# Endstops.net
KiCad netlist of a schematic drawn in Altium Designer
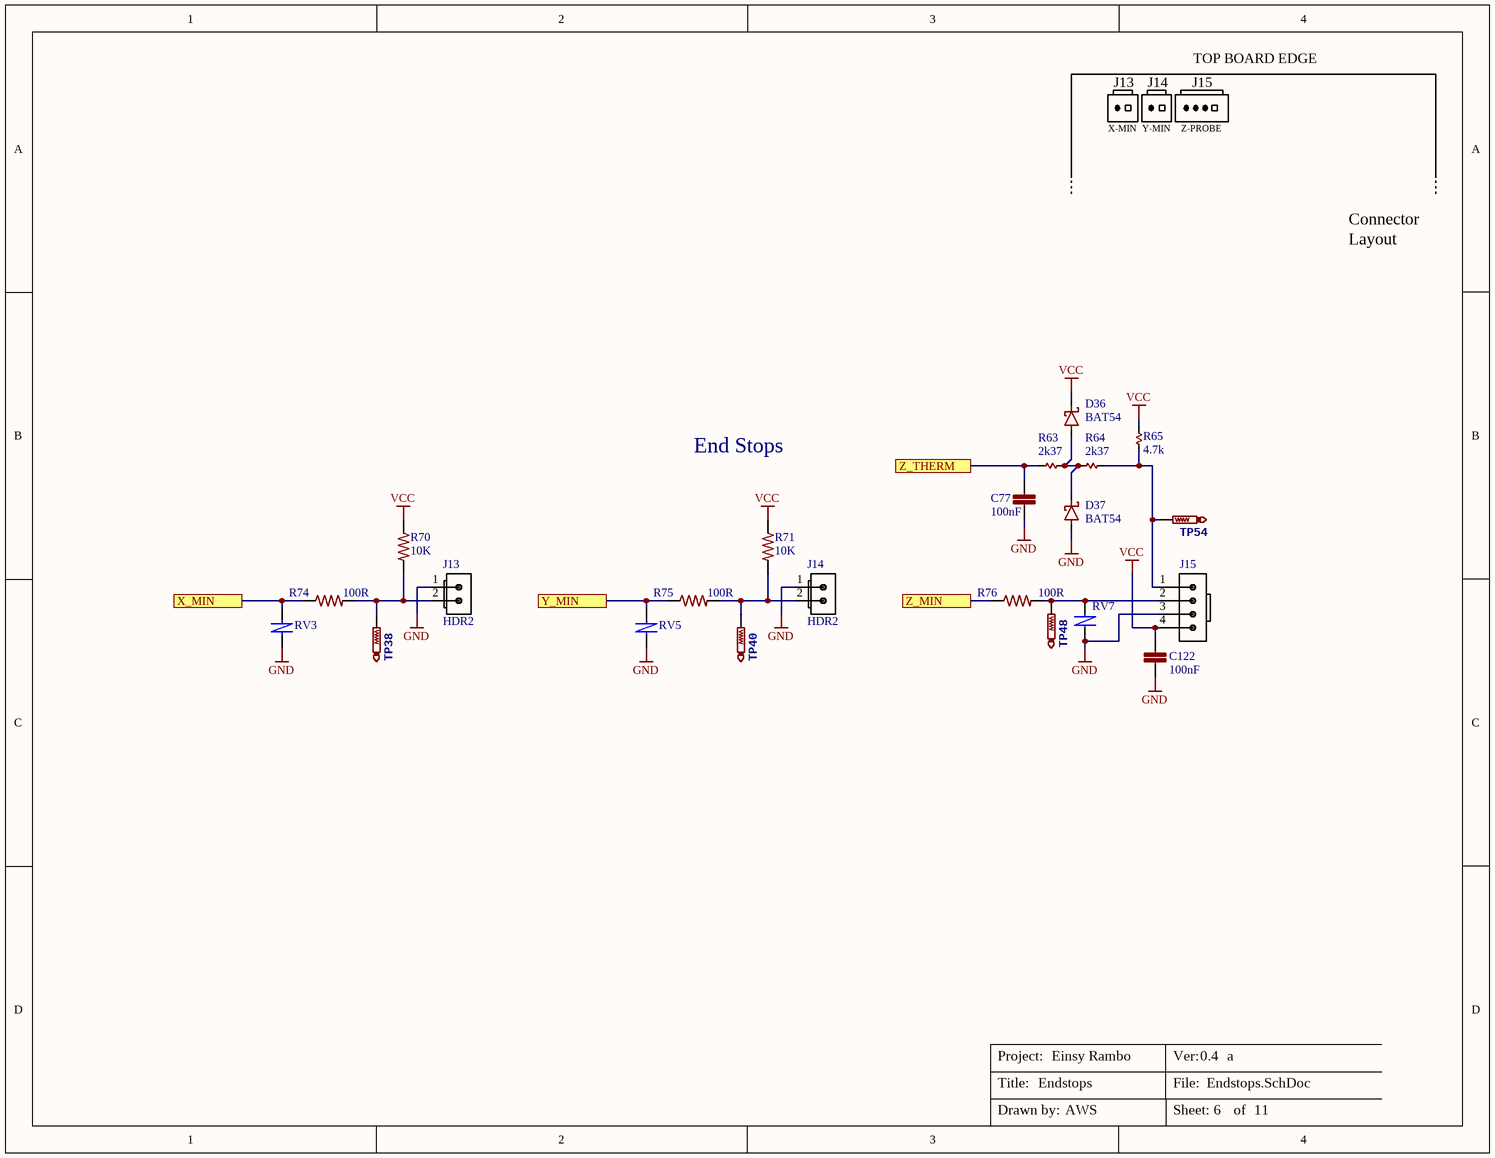
[diagram p0: Endstops.SchDoc]

(export (version "E")
  (design (tool "Eeschema 10.0.6"))
  (components
    (comp (ref "C77")
      (value "100nF")
      (footprint "C0402")
      (description "CAP CER 0402 100nF 16V 10% X7R")
      (fields (field (name "MANUFACTURER") "Murata") (field (name "TOLERANCE") "+/- 10%"))
      (libsource (lib "") (part "GRM155R71C104KA88D_1"))
    )
    (comp (ref "C122")
      (value "100nF")
      (footprint "C0402")
      (description "CAP CER 0402 100nF 16V 10% X7R")
      (fields (field (name "MANUFACTURER") "Murata") (field (name "TOLERANCE") "+/- 10%"))
      (libsource (lib "3Delight") (part "GRM155R71C104KA88D"))
    )
    (comp (ref "D36")
      (value "BAT54")
      (footprint "SOD523_IPC")
      (description "Diode Schottky 30V 100mA Surface Mount SOD-523")
      (fields (field (name "MANUFACTURER") "Diodes Incorporated") (field (name "TOLERANCE") "NA"))
      (libsource (lib "3Delight") (part "BAT54WT-7"))
    )
    (comp (ref "D37")
      (value "BAT54")
      (footprint "SOD523_IPC")
      (description "Diode Schottky 30V 100mA Surface Mount SOD-523")
      (fields (field (name "MANUFACTURER") "Diodes Incorporated") (field (name "TOLERANCE") "NA"))
      (libsource (lib "3Delight") (part "BAT54WT-7"))
    )
    (comp (ref "J13")
      (value "HDR2")
      (footprint "70543-02 PIN-IN-PASTE")
      (description "Connector 2pos")
      (fields (field (name "MANUFACTURER") "Molex") (field (name "PART") "2 Pin Conn"))
      (libsource (lib "Connectors") (part "CONN 2PIN VERT 0.1{dblquote} SHRD LOCKING PIN-IN-PASTE"))
    )
    (comp (ref "J14")
      (value "HDR2")
      (footprint "70543-02 PIN-IN-PASTE")
      (description "Connector 2pos")
      (fields (field (name "MANUFACTURER") "Molex") (field (name "PART") "2 Pin Conn"))
      (libsource (lib "Connectors") (part "CONN 2PIN VERT 0.1{dblquote} SHRD LOCKING PIN-IN-PASTE"))
    )
    (comp (ref "J15")
      (value "Molex 0705430003")
      (footprint "4POL254 PIN-IN-PASTE")
      (description "Molex 4 Pin Clip Connector")
      (libsource (lib "Connectors") (part "Molex 0705430003 PIN-IN-PASTE"))
    )
    (comp (ref "R63")
      (value "2k37")
      (footprint "R0402")
      (description "RES SMD 2.37K OHM 1% 1/16W 0402")
      (fields (field (name "MANUFACTURER") "Yageo") (field (name "PART") "2.37k"))
      (libsource (lib "3Delight") (part "RC0402FR-072K37L"))
    )
    (comp (ref "R64")
      (value "2k37")
      (footprint "R0402")
      (description "RES SMD 2.37K OHM 1% 1/16W 0402")
      (fields (field (name "MANUFACTURER") "Yageo") (field (name "PART") "2.37k"))
      (libsource (lib "3Delight") (part "RC0402FR-072K37L"))
    )
    (comp (ref "R65")
      (value "4.7k")
      (footprint "R0402")
      (description "RES SMD 4.7K OHM 1% 1/16W 0402")
      (fields (field (name "MANUFACTURER") "Yageo") (field (name "TOLERANCE") "+/- 1%"))
      (libsource (lib "3Delight") (part "RC0402FR-074K7L"))
    )
    (comp (ref "R70")
      (value "10K")
      (footprint "R0402")
      (description "RES SMD 10K OHM 1% 1/16W 0402")
      (fields (field (name "MANUFACTURER") "Yageo") (field (name "PART") "10k 1% 0402"))
      (libsource (lib "3Delight") (part "RC0402FR-0710KP"))
    )
    (comp (ref "R71")
      (value "10K")
      (footprint "R0402")
      (description "RES SMD 10K OHM 1% 1/16W 0402")
      (fields (field (name "MANUFACTURER") "Yageo") (field (name "PART") "10k 1% 0402"))
      (libsource (lib "3Delight") (part "RC0402FR-0710KP"))
    )
    (comp (ref "R74")
      (value "100R")
      (footprint "R0402")
      (description "RES SMD 100 OHM 1% 1/16W 0402")
      (fields (field (name "MANUFACTURER") "Yageo") (field (name "PART") "100R 1% 0402"))
      (libsource (lib "Archim") (part "RES 100R 0402 1%"))
    )
    (comp (ref "R75")
      (value "100R")
      (footprint "R0402")
      (description "RES SMD 100 OHM 1% 1/16W 0402")
      (fields (field (name "MANUFACTURER") "Yageo") (field (name "PART") "100R 1% 0402"))
      (libsource (lib "Archim") (part "RES 100R 0402 1%"))
    )
    (comp (ref "R76")
      (value "100R")
      (footprint "R0402")
      (description "RES SMD 100 OHM 1% 1/16W 0402")
      (fields (field (name "MANUFACTURER") "Yageo") (field (name "PART") "100R 1% 0402"))
      (libsource (lib "Archim") (part "RES 100R 0402 1%"))
    )
    (comp (ref "RV3")
      (value "VRS0402SR55R101N")
      (footprint "C0402")
      (description "Multi-Layer Varistor")
      (fields (field (name "MANUFACTURER") "Yageo") (field (name "PART") "12V"))
      (libsource (lib "3Delight") (part "VRS0402SR55R101N"))
    )
    (comp (ref "RV5")
      (value "VRS0402SR55R101N")
      (footprint "C0402")
      (description "Multi-Layer Varistor")
      (fields (field (name "MANUFACTURER") "Yageo") (field (name "PART") "12V"))
      (libsource (lib "3Delight") (part "VRS0402SR55R101N"))
    )
    (comp (ref "RV7")
      (value "VRS0402SR55R101N")
      (footprint "C0402")
      (description "Multi-Layer Varistor")
      (fields (field (name "MANUFACTURER") "Yageo") (field (name "PART") "12V"))
      (libsource (lib "3Delight") (part "VRS0402SR55R101N"))
    )
    (comp (ref "TP38")
      (value "TestPoint")
      (footprint "TP1-27")
      (description "Test Point")
      (libsource (lib "") (part "TestPoint_1"))
    )
    (comp (ref "TP40")
      (value "TestPoint")
      (footprint "TP1-27")
      (description "Test Point")
      (libsource (lib "") (part "TestPoint_1"))
    )
    (comp (ref "TP48")
      (value "TestPoint")
      (footprint "TP1-27")
      (description "Test Point")
      (libsource (lib "") (part "TestPoint_1"))
    )
    (comp (ref "TP54")
      (value "TestPoint")
      (footprint "TP1-27")
      (description "Test Point")
      (libsource (lib "3Delight") (part "TestPoint"))
    )
  )
  (nets
    (net (code "1") (name "/X_MIN") (class "Default")
      (node (ref "R74") (pin "1") (pinfunction "1_1") (pintype "passive"))
      (node (ref "RV3") (pin "2") (pinfunction "2_2") (pintype "passive"))
    )
    (net (code "2") (name "/Y_MIN") (class "Default")
      (node (ref "R75") (pin "1") (pinfunction "1_1") (pintype "passive"))
      (node (ref "RV5") (pin "2") (pinfunction "2_2") (pintype "passive"))
    )
    (net (code "3") (name "/Z_MIN") (class "Default")
      (node (ref "R76") (pin "1") (pinfunction "1_1") (pintype "passive"))
    )
    (net (code "4") (name "/Z_THERM") (class "Default")
      (node (ref "C77") (pin "1") (pinfunction "1_1") (pintype "passive"))
      (node (ref "R63") (pin "2") (pinfunction "2_2") (pintype "passive"))
    )
    (net (code "5") (name "GND") (class "Default")
      (node (ref "C122") (pin "1") (pinfunction "1_1") (pintype "passive"))
      (node (ref "C77") (pin "2") (pinfunction "2_2") (pintype "passive"))
      (node (ref "D37") (pin "A") (pinfunction "A_A") (pintype "passive"))
      (node (ref "J13") (pin "1") (pinfunction "S_1") (pintype "passive"))
      (node (ref "J14") (pin "1") (pinfunction "S_1") (pintype "passive"))
      (node (ref "J15") (pin "3") (pinfunction "3_3") (pintype "passive"))
      (node (ref "RV3") (pin "1") (pinfunction "1_1") (pintype "passive"))
      (node (ref "RV5") (pin "1") (pinfunction "1_1") (pintype "passive"))
      (node (ref "RV7") (pin "1") (pinfunction "1_1") (pintype "passive"))
    )
    (net (code "6") (name "Net-(D36-PadA)") (class "Default")
      (node (ref "D36") (pin "A") (pinfunction "A_A") (pintype "passive"))
      (node (ref "D37") (pin "K") (pinfunction "K_K") (pintype "passive"))
      (node (ref "R63") (pin "1") (pinfunction "1_1") (pintype "passive"))
      (node (ref "R64") (pin "2") (pinfunction "2_2") (pintype "passive"))
    )
    (net (code "7") (name "Net-(J13-S-Pad2)") (class "Default")
      (node (ref "J13") (pin "2") (pinfunction "S_2") (pintype "passive"))
      (node (ref "R70") (pin "2") (pinfunction "2_2") (pintype "passive"))
      (node (ref "R74") (pin "2") (pinfunction "2_2") (pintype "passive"))
      (node (ref "TP38") (pin "TP") (pinfunction "TP_TP") (pintype "passive"))
    )
    (net (code "8") (name "Net-(J14-S-Pad2)") (class "Default")
      (node (ref "J14") (pin "2") (pinfunction "S_2") (pintype "passive"))
      (node (ref "R71") (pin "2") (pinfunction "2_2") (pintype "passive"))
      (node (ref "R75") (pin "2") (pinfunction "2_2") (pintype "passive"))
      (node (ref "TP40") (pin "TP") (pinfunction "TP_TP") (pintype "passive"))
    )
    (net (code "9") (name "Net-(J15-Pad1)") (class "Default")
      (node (ref "J15") (pin "1") (pinfunction "1_1") (pintype "passive"))
      (node (ref "R64") (pin "1") (pinfunction "1_1") (pintype "passive"))
      (node (ref "R65") (pin "1") (pinfunction "1_1") (pintype "passive"))
      (node (ref "TP54") (pin "TP") (pinfunction "TP_TP") (pintype "passive"))
    )
    (net (code "10") (name "Net-(J15-Pad2)") (class "Default")
      (node (ref "J15") (pin "2") (pinfunction "2_2") (pintype "passive"))
      (node (ref "R76") (pin "2") (pinfunction "2_2") (pintype "passive"))
      (node (ref "RV7") (pin "2") (pinfunction "2_2") (pintype "passive"))
      (node (ref "TP48") (pin "TP") (pinfunction "TP_TP") (pintype "passive"))
    )
    (net (code "11") (name "VCC") (class "Default")
      (node (ref "C122") (pin "2") (pinfunction "2_2") (pintype "passive"))
      (node (ref "D36") (pin "K") (pinfunction "K_K") (pintype "passive"))
      (node (ref "J15") (pin "4") (pinfunction "4_4") (pintype "passive"))
      (node (ref "R65") (pin "2") (pinfunction "2_2") (pintype "passive"))
      (node (ref "R70") (pin "1") (pinfunction "1_1") (pintype "passive"))
      (node (ref "R71") (pin "1") (pinfunction "1_1") (pintype "passive"))
    )
  )
)
